# USB-Connection.net
KiCad netlist of a schematic drawn in Altium Designer
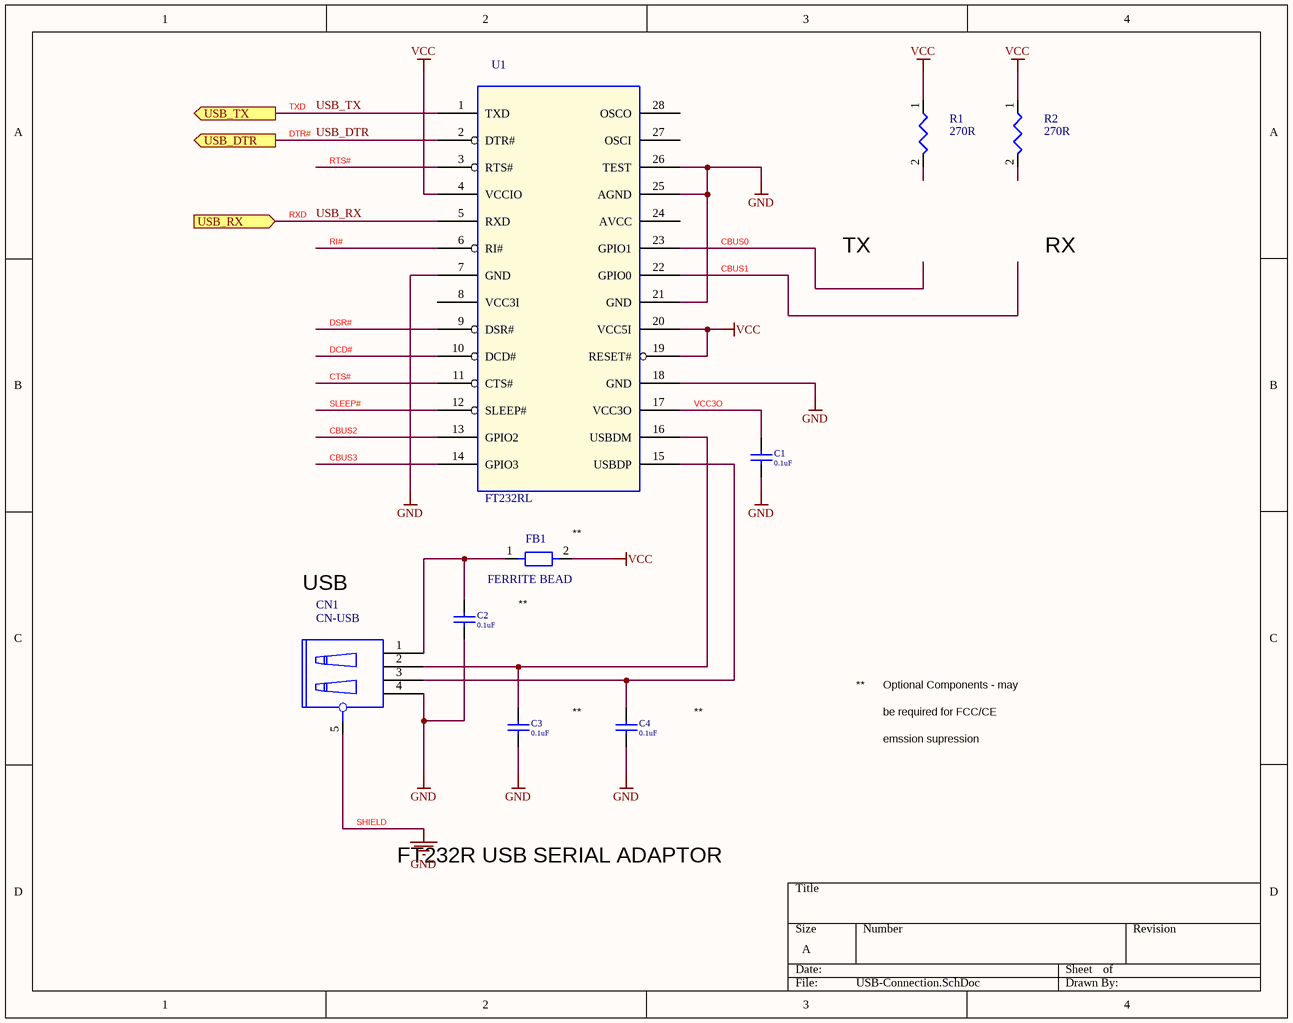
[diagram p0: USB-Connection.SchDoc]

(export (version "E")
  (design (tool "Eeschema 10.0.6"))
  (components
    (comp (ref "C1")
      (value "0.1uF")
      (footprint "SMD 0805 CAP")
      (description "Capacitor")
      (fields (field (name "PUBLISHER") "Altium Limited"))
      (libsource (lib "DIY-USB Led Controller") (part "Cap_3"))
    )
    (comp (ref "C2")
      (value "0.1uF")
      (footprint "SMD 0805 CAP")
      (description "Capacitor")
      (fields (field (name "PUBLISHER") "Altium Limited"))
      (libsource (lib "DIY-USB Led Controller") (part "Cap_3"))
    )
    (comp (ref "C3")
      (value "0.1uF")
      (footprint "SMD 0805 CAP")
      (description "Capacitor")
      (fields (field (name "PUBLISHER") "Altium Limited"))
      (libsource (lib "DIY-USB Led Controller") (part "Cap_3"))
    )
    (comp (ref "C4")
      (value "0.1uF")
      (footprint "SMD 0805 CAP")
      (description "Capacitor")
      (fields (field (name "PUBLISHER") "Altium Limited"))
      (libsource (lib "DIY-USB Led Controller") (part "Cap_3"))
    )
    (comp (ref "CN1")
      (value "CN-USB")
      (footprint "FCI USB 61729-1011BLF")
      (libsource (lib "DIY-USB Led Controller") (part "CN-USB"))
    )
    (comp (ref "FB1") (value "FERRITE BEAD") (libsource (lib "*") (part "FB")))
    (comp (ref "R1") (value "270R") (libsource (lib "*") (part "R")))
    (comp (ref "R2") (value "270R") (libsource (lib "*") (part "R")))
    (comp (ref "U1")
      (value "FT232RL")
      (footprint "28-SSOP")
      (description "USB Bridge, USB to UART USB 2.0 UART Interface 28-SSOP")
      (libsource (lib "*") (part "FT232R"))
    )
  )
  (nets
    (net (code "1") (name "/CBUS0") (class "Default")
      (node (ref "U1") (pin "23") (pinfunction "GPIO1_23") (pintype "passive"))
    )
    (net (code "2") (name "/CBUS1") (class "Default")
      (node (ref "U1") (pin "22") (pinfunction "GPIO0_22") (pintype "passive"))
    )
    (net (code "3") (name "/CBUS2") (class "Default")
      (node (ref "U1") (pin "13") (pinfunction "GPIO2_13") (pintype "passive"))
    )
    (net (code "4") (name "/CBUS3") (class "Default")
      (node (ref "U1") (pin "14") (pinfunction "GPIO3_14") (pintype "passive"))
    )
    (net (code "5") (name "/CTS#") (class "Default")
      (node (ref "U1") (pin "11") (pinfunction "CTS#_11") (pintype "passive"))
    )
    (net (code "6") (name "/DCD#") (class "Default")
      (node (ref "U1") (pin "10") (pinfunction "DCD#_10") (pintype "passive"))
    )
    (net (code "7") (name "/DSR#") (class "Default")
      (node (ref "U1") (pin "9") (pinfunction "DSR#_9") (pintype "passive"))
    )
    (net (code "8") (name "/DTR#") (class "Default")
      (node (ref "U1") (pin "2") (pinfunction "DTR#_2") (pintype "passive"))
    )
    (net (code "9") (name "/RI#") (class "Default")
      (node (ref "U1") (pin "6") (pinfunction "RI#_6") (pintype "passive"))
    )
    (net (code "10") (name "/RTS#") (class "Default")
      (node (ref "U1") (pin "3") (pinfunction "RTS#_3") (pintype "passive"))
    )
    (net (code "11") (name "/RXD") (class "Default")
      (node (ref "U1") (pin "5") (pinfunction "RXD_5") (pintype "passive"))
    )
    (net (code "12") (name "/SLEEP#") (class "Default")
      (node (ref "U1") (pin "12") (pinfunction "SLEEP#_12") (pintype "passive"))
    )
    (net (code "13") (name "/TXD") (class "Default")
      (node (ref "U1") (pin "1") (pinfunction "TXD_1") (pintype "passive"))
    )
    (net (code "14") (name "/VCC3O") (class "Default")
      (node (ref "C1") (pin "2") (pinfunction "2_2") (pintype "passive"))
      (node (ref "U1") (pin "17") (pinfunction "VCC3O_17") (pintype "passive"))
    )
    (net (code "15") (name "GND") (class "Default")
      (node (ref "C1") (pin "1") (pinfunction "1_1") (pintype "passive"))
      (node (ref "C2") (pin "1") (pinfunction "1_1") (pintype "passive"))
      (node (ref "C3") (pin "1") (pinfunction "1_1") (pintype "passive"))
      (node (ref "C4") (pin "1") (pinfunction "1_1") (pintype "passive"))
      (node (ref "CN1") (pin "4") (pinfunction "4_4") (pintype "passive"))
      (node (ref "CN1") (pin "5") (pinfunction "5_5") (pintype "passive"))
      (node (ref "U1") (pin "18") (pinfunction "GND_18") (pintype "passive"))
      (node (ref "U1") (pin "21") (pinfunction "GND_21") (pintype "passive"))
      (node (ref "U1") (pin "25") (pinfunction "AGND_25") (pintype "passive"))
      (node (ref "U1") (pin "26") (pinfunction "TEST_26") (pintype "passive"))
      (node (ref "U1") (pin "7") (pinfunction "GND_7") (pintype "passive"))
    )
    (net (code "16") (name "Net-(C2-Pad2)") (class "Default")
      (node (ref "C2") (pin "2") (pinfunction "2_2") (pintype "passive"))
      (node (ref "CN1") (pin "1") (pinfunction "1_1") (pintype "passive"))
      (node (ref "FB1") (pin "1") (pinfunction "1_1") (pintype "passive"))
    )
    (net (code "17") (name "Net-(U1-USBDM)") (class "Default")
      (node (ref "C3") (pin "2") (pinfunction "2_2") (pintype "passive"))
      (node (ref "CN1") (pin "2") (pinfunction "2_2") (pintype "passive"))
      (node (ref "U1") (pin "16") (pinfunction "USBDM_16") (pintype "passive"))
    )
    (net (code "18") (name "Net-(U1-USBDP)") (class "Default")
      (node (ref "C4") (pin "2") (pinfunction "2_2") (pintype "passive"))
      (node (ref "CN1") (pin "3") (pinfunction "3_3") (pintype "passive"))
      (node (ref "U1") (pin "15") (pinfunction "USBDP_15") (pintype "passive"))
    )
    (net (code "19") (name "VCC") (class "Default")
      (node (ref "FB1") (pin "2") (pinfunction "2_2") (pintype "passive"))
      (node (ref "R1") (pin "1") (pinfunction "1_1") (pintype "passive"))
      (node (ref "R2") (pin "1") (pinfunction "1_1") (pintype "passive"))
      (node (ref "U1") (pin "19") (pinfunction "RESET#_19") (pintype "passive"))
      (node (ref "U1") (pin "20") (pinfunction "VCC5I_20") (pintype "passive"))
      (node (ref "U1") (pin "4") (pinfunction "VCCIO_4") (pintype "passive"))
    )
    (net (code "20") (name "unconnected-(R1-Pad2)") (class "Default")
      (node (ref "R1") (pin "2") (pinfunction "2_2") (pintype "passive"))
    )
    (net (code "21") (name "unconnected-(R2-Pad2)") (class "Default")
      (node (ref "R2") (pin "2") (pinfunction "2_2") (pintype "passive"))
    )
    (net (code "22") (name "unconnected-(U1-AVCC-Pad24)") (class "Default")
      (node (ref "U1") (pin "24") (pinfunction "AVCC_24") (pintype "passive"))
    )
    (net (code "23") (name "unconnected-(U1-OSCI-Pad27)") (class "Default")
      (node (ref "U1") (pin "27") (pinfunction "OSCI_27") (pintype "passive"))
    )
    (net (code "24") (name "unconnected-(U1-OSCO-Pad28)") (class "Default")
      (node (ref "U1") (pin "28") (pinfunction "OSCO_28") (pintype "passive"))
    )
    (net (code "25") (name "unconnected-(U1-VCC3I-Pad8)") (class "Default")
      (node (ref "U1") (pin "8") (pinfunction "VCC3I_8") (pintype "passive"))
    )
  )
)
